# LVDS_Receiver_Data.net
KiCad netlist of a schematic drawn in Altium Designer
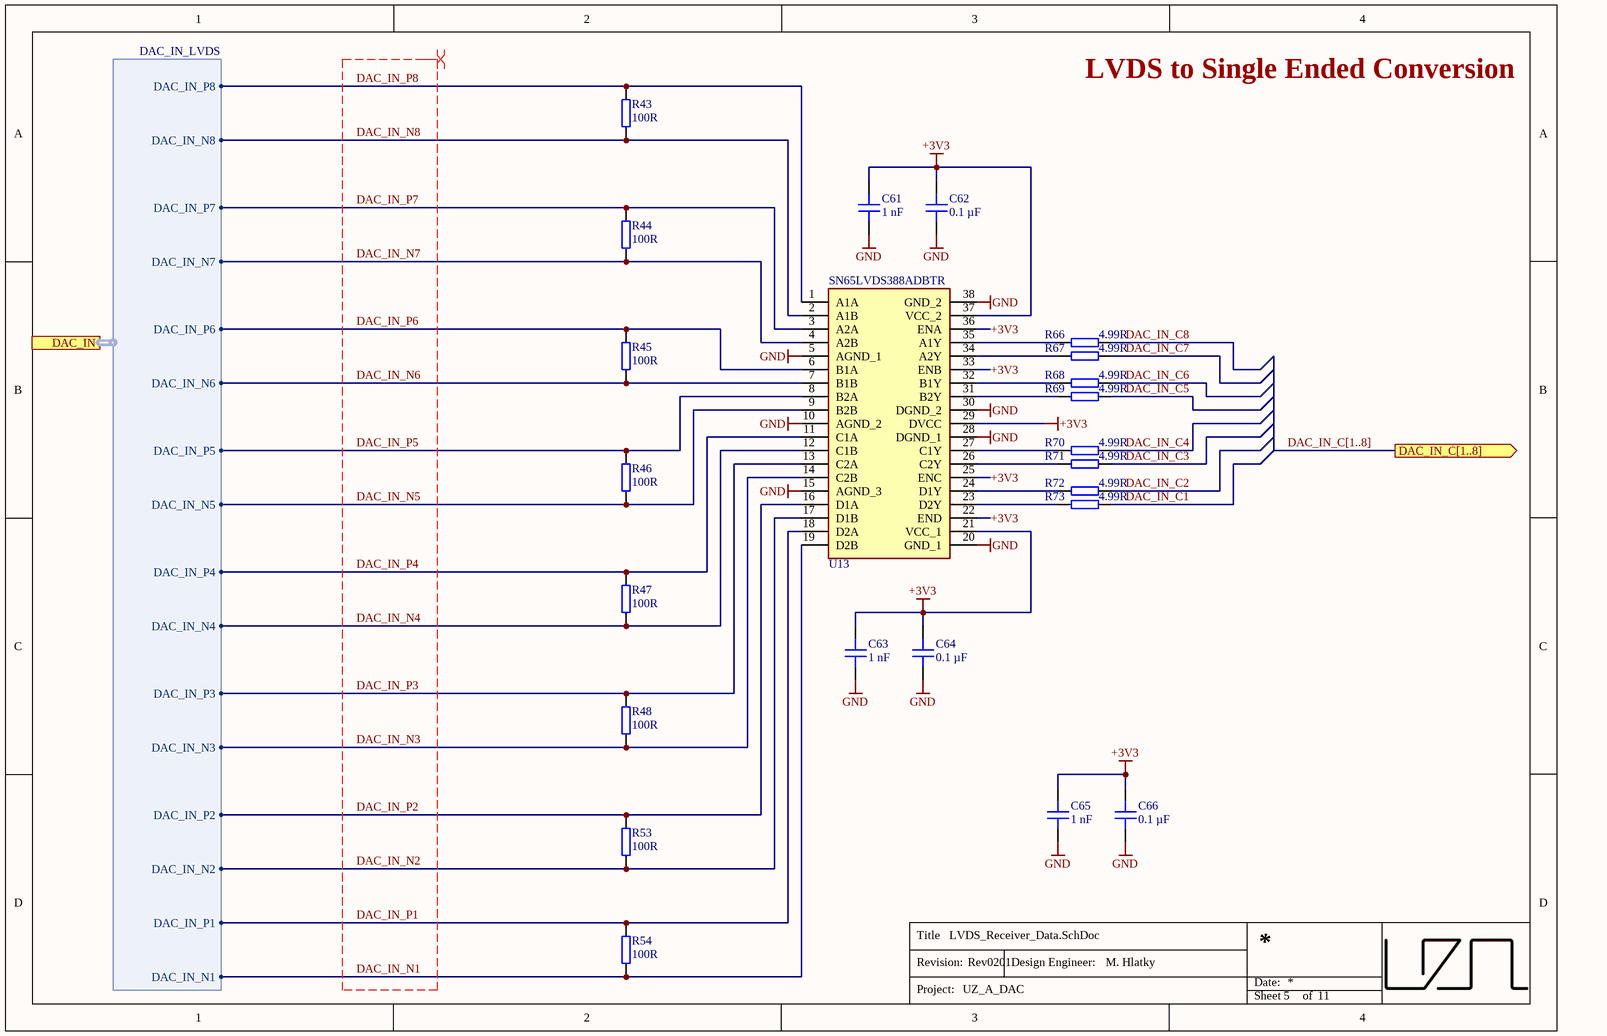
[diagram p0: LVDS_Receiver_Data.SchDoc]

(export (version "E")
  (design (tool "Eeschema 10.0.6"))
  (components
    (comp (ref "C61")
      (value "1 nF")
      (footprint "C_1206")
      (description "Capacitor 1206, 50 VDC, 1 nF, X7R")
      (fields
        (field (name "MANUFACTURER PART NUMBER") "12065C102KAT2A")
        (field (name "MANUFACTURER") "AVX")
        (field (name "CREATED FROM") "MGremer")
      )
      (libsource (lib "user") (part "Capacitor"))
    )
    (comp (ref "C62")
      (value "0.1 µF")
      (footprint "C_0603")
      (description "Capacitor 0603, 50 VDC, 0.1 µF, X7R")
      (fields
        (field (name "MANUFACTURER PART NUMBER") "C0603X104K5RAC7411")
        (field (name "MANUFACTURER") "KEMET")
        (field (name "CREATED FROM") "MGremer")
      )
      (libsource (lib "user") (part "Capacitor"))
    )
    (comp (ref "C63")
      (value "1 nF")
      (footprint "C_1206")
      (description "Capacitor 1206, 50 VDC, 1 nF, X7R")
      (fields
        (field (name "MANUFACTURER PART NUMBER") "12065C102KAT2A")
        (field (name "MANUFACTURER") "AVX")
        (field (name "CREATED FROM") "MGremer")
      )
      (libsource (lib "user") (part "Capacitor"))
    )
    (comp (ref "C64")
      (value "0.1 µF")
      (footprint "C_0603")
      (description "Capacitor 0603, 50 VDC, 0.1 µF, X7R")
      (fields
        (field (name "MANUFACTURER PART NUMBER") "C0603X104K5RAC7411")
        (field (name "MANUFACTURER") "KEMET")
        (field (name "CREATED FROM") "MGremer")
      )
      (libsource (lib "user") (part "Capacitor"))
    )
    (comp (ref "C65")
      (value "1 nF")
      (footprint "C_1206")
      (description "Capacitor 1206, 50 VDC, 1 nF, X7R")
      (fields
        (field (name "MANUFACTURER PART NUMBER") "12065C102KAT2A")
        (field (name "MANUFACTURER") "AVX")
        (field (name "CREATED FROM") "MGremer")
      )
      (libsource (lib "user") (part "Capacitor"))
    )
    (comp (ref "C66")
      (value "0.1 µF")
      (footprint "C_0603")
      (description "Capacitor 0603, 50 VDC, 0.1 µF, X7R")
      (fields
        (field (name "MANUFACTURER PART NUMBER") "C0603X104K5RAC7411")
        (field (name "MANUFACTURER") "KEMET")
        (field (name "CREATED FROM") "MGremer")
      )
      (libsource (lib "user") (part "Capacitor"))
    )
    (comp (ref "R43")
      (value "100R")
      (footprint "RES 0603_1608")
      (description "SMD resistor 1%")
      (fields
        (field (name "MANUFACTURER PART NUMBER") "AC0603FR-13100RL")
        (field (name "MANUFACTURER") "Yageo")
        (field (name "CREATED FROM") "MGremer")
      )
      (libsource (lib "user") (part "Resistor"))
    )
    (comp (ref "R44")
      (value "100R")
      (footprint "RES 0603_1608")
      (description "SMD resistor 1%")
      (fields
        (field (name "MANUFACTURER PART NUMBER") "AC0603FR-13100RL")
        (field (name "MANUFACTURER") "Yageo")
        (field (name "CREATED FROM") "MGremer")
      )
      (libsource (lib "user") (part "Resistor"))
    )
    (comp (ref "R45")
      (value "100R")
      (footprint "RES 0603_1608")
      (description "SMD resistor 1%")
      (fields
        (field (name "MANUFACTURER PART NUMBER") "AC0603FR-13100RL")
        (field (name "MANUFACTURER") "Yageo")
        (field (name "CREATED FROM") "MGremer")
      )
      (libsource (lib "user") (part "Resistor"))
    )
    (comp (ref "R46")
      (value "100R")
      (footprint "RES 0603_1608")
      (description "SMD resistor 1%")
      (fields
        (field (name "MANUFACTURER PART NUMBER") "AC0603FR-13100RL")
        (field (name "MANUFACTURER") "Yageo")
        (field (name "CREATED FROM") "MGremer")
      )
      (libsource (lib "user") (part "Resistor"))
    )
    (comp (ref "R47")
      (value "100R")
      (footprint "RES 0603_1608")
      (description "SMD resistor 1%")
      (fields
        (field (name "MANUFACTURER PART NUMBER") "AC0603FR-13100RL")
        (field (name "MANUFACTURER") "Yageo")
        (field (name "CREATED FROM") "MGremer")
      )
      (libsource (lib "user") (part "Resistor"))
    )
    (comp (ref "R48")
      (value "100R")
      (footprint "RES 0603_1608")
      (description "SMD resistor 1%")
      (fields
        (field (name "MANUFACTURER PART NUMBER") "AC0603FR-13100RL")
        (field (name "MANUFACTURER") "Yageo")
        (field (name "CREATED FROM") "MGremer")
      )
      (libsource (lib "user") (part "Resistor"))
    )
    (comp (ref "R53")
      (value "100R")
      (footprint "RES 0603_1608")
      (description "SMD resistor 1%")
      (fields
        (field (name "MANUFACTURER PART NUMBER") "AC0603FR-13100RL")
        (field (name "MANUFACTURER") "Yageo")
        (field (name "CREATED FROM") "MGremer")
      )
      (libsource (lib "user") (part "Resistor"))
    )
    (comp (ref "R54")
      (value "100R")
      (footprint "RES 0603_1608")
      (description "SMD resistor 1%")
      (fields
        (field (name "MANUFACTURER PART NUMBER") "AC0603FR-13100RL")
        (field (name "MANUFACTURER") "Yageo")
        (field (name "CREATED FROM") "MGremer")
      )
      (libsource (lib "user") (part "Resistor"))
    )
    (comp (ref "R66")
      (value "4.99R")
      (footprint "RES 0603_1608")
      (description "SMD resistor 1%")
      (fields
        (field (name "MANUFACTURER PART NUMBER") "CRCW06034R99FKEA")
        (field (name "MANUFACTURER") "Vishay / Dale")
        (field (name "CREATED FROM") "MGremer")
      )
      (libsource (lib "user") (part "Resistor"))
    )
    (comp (ref "R67")
      (value "4.99R")
      (footprint "RES 0603_1608")
      (description "SMD resistor 1%")
      (fields
        (field (name "MANUFACTURER PART NUMBER") "CRCW06034R99FKEA")
        (field (name "MANUFACTURER") "Vishay / Dale")
        (field (name "CREATED FROM") "MGremer")
      )
      (libsource (lib "user") (part "Resistor"))
    )
    (comp (ref "R68")
      (value "4.99R")
      (footprint "RES 0603_1608")
      (description "SMD resistor 1%")
      (fields
        (field (name "MANUFACTURER PART NUMBER") "CRCW06034R99FKEA")
        (field (name "MANUFACTURER") "Vishay / Dale")
        (field (name "CREATED FROM") "MGremer")
      )
      (libsource (lib "user") (part "Resistor"))
    )
    (comp (ref "R69")
      (value "4.99R")
      (footprint "RES 0603_1608")
      (description "SMD resistor 1%")
      (fields
        (field (name "MANUFACTURER PART NUMBER") "CRCW06034R99FKEA")
        (field (name "MANUFACTURER") "Vishay / Dale")
        (field (name "CREATED FROM") "MGremer")
      )
      (libsource (lib "user") (part "Resistor"))
    )
    (comp (ref "R70")
      (value "4.99R")
      (footprint "RES 0603_1608")
      (description "SMD resistor 1%")
      (fields
        (field (name "MANUFACTURER PART NUMBER") "CRCW06034R99FKEA")
        (field (name "MANUFACTURER") "Vishay / Dale")
        (field (name "CREATED FROM") "MGremer")
      )
      (libsource (lib "user") (part "Resistor"))
    )
    (comp (ref "R71")
      (value "4.99R")
      (footprint "RES 0603_1608")
      (description "SMD resistor 1%")
      (fields
        (field (name "MANUFACTURER PART NUMBER") "CRCW06034R99FKEA")
        (field (name "MANUFACTURER") "Vishay / Dale")
        (field (name "CREATED FROM") "MGremer")
      )
      (libsource (lib "user") (part "Resistor"))
    )
    (comp (ref "R72")
      (value "4.99R")
      (footprint "RES 0603_1608")
      (description "SMD resistor 1%")
      (fields
        (field (name "MANUFACTURER PART NUMBER") "CRCW06034R99FKEA")
        (field (name "MANUFACTURER") "Vishay / Dale")
        (field (name "CREATED FROM") "MGremer")
      )
      (libsource (lib "user") (part "Resistor"))
    )
    (comp (ref "R73")
      (value "4.99R")
      (footprint "RES 0603_1608")
      (description "SMD resistor 1%")
      (fields
        (field (name "MANUFACTURER PART NUMBER") "CRCW06034R99FKEA")
        (field (name "MANUFACTURER") "Vishay / Dale")
        (field (name "CREATED FROM") "MGremer")
      )
      (libsource (lib "user") (part "Resistor"))
    )
    (comp (ref "U13")
      (value "SN65LVDS388ADBTR")
      (footprint "SOP50P640X120-38N")
      (description "High-Speed Differential Line Receivers")
      (fields (field (name "MANUFACTURER") "TI") (field (name "CREATED FROM") "MHlatky"))
      (libsource (lib "user") (part "SN65LVDS388ADBTR"))
    )
  )
  (nets
    (net (code "2") (name "+3V3") (class "Default")
      (node (ref "C61") (pin "2") (pinfunction "2_2") (pintype "passive"))
      (node (ref "C62") (pin "1") (pinfunction "1_1") (pintype "passive"))
      (node (ref "C63") (pin "2") (pinfunction "2_2") (pintype "passive"))
      (node (ref "C64") (pin "1") (pinfunction "1_1") (pintype "passive"))
      (node (ref "C65") (pin "2") (pinfunction "2_2") (pintype "passive"))
      (node (ref "C66") (pin "1") (pinfunction "1_1") (pintype "passive"))
      (node (ref "U13") (pin "21") (pinfunction "VCC_1_21") (pintype "passive"))
      (node (ref "U13") (pin "22") (pinfunction "END_22") (pintype "passive"))
      (node (ref "U13") (pin "25") (pinfunction "ENC_25") (pintype "passive"))
      (node (ref "U13") (pin "29") (pinfunction "DVCC_29") (pintype "passive"))
      (node (ref "U13") (pin "33") (pinfunction "ENB_33") (pintype "passive"))
      (node (ref "U13") (pin "36") (pinfunction "ENA_36") (pintype "passive"))
      (node (ref "U13") (pin "37") (pinfunction "VCC_2_37") (pintype "passive"))
    )
    (net (code "3") (name "/DAC_IN_C1") (class "Default")
      (node (ref "R73") (pin "2") (pinfunction "2_2") (pintype "passive"))
    )
    (net (code "4") (name "/DAC_IN_C2") (class "Default")
      (node (ref "R72") (pin "2") (pinfunction "2_2") (pintype "passive"))
    )
    (net (code "5") (name "/DAC_IN_C3") (class "Default")
      (node (ref "R71") (pin "2") (pinfunction "2_2") (pintype "passive"))
    )
    (net (code "6") (name "/DAC_IN_C4") (class "Default")
      (node (ref "R70") (pin "2") (pinfunction "2_2") (pintype "passive"))
    )
    (net (code "7") (name "/DAC_IN_C5") (class "Default")
      (node (ref "R69") (pin "2") (pinfunction "2_2") (pintype "passive"))
    )
    (net (code "8") (name "/DAC_IN_C6") (class "Default")
      (node (ref "R68") (pin "2") (pinfunction "2_2") (pintype "passive"))
    )
    (net (code "9") (name "/DAC_IN_C7") (class "Default")
      (node (ref "R67") (pin "2") (pinfunction "2_2") (pintype "passive"))
    )
    (net (code "10") (name "/DAC_IN_C8") (class "Default")
      (node (ref "R66") (pin "2") (pinfunction "2_2") (pintype "passive"))
    )
    (net (code "12") (name "/DAC_IN_N1") (class "Default")
      (node (ref "R54") (pin "1") (pinfunction "1_1") (pintype "passive"))
      (node (ref "U13") (pin "19") (pinfunction "D2B_19") (pintype "passive"))
    )
    (net (code "13") (name "/DAC_IN_N2") (class "Default")
      (node (ref "R53") (pin "1") (pinfunction "1_1") (pintype "passive"))
      (node (ref "U13") (pin "17") (pinfunction "D1B_17") (pintype "passive"))
    )
    (net (code "14") (name "/DAC_IN_N3") (class "Default")
      (node (ref "R48") (pin "1") (pinfunction "1_1") (pintype "passive"))
      (node (ref "U13") (pin "14") (pinfunction "C2B_14") (pintype "passive"))
    )
    (net (code "15") (name "/DAC_IN_N4") (class "Default")
      (node (ref "R47") (pin "1") (pinfunction "1_1") (pintype "passive"))
      (node (ref "U13") (pin "12") (pinfunction "C1B_12") (pintype "passive"))
    )
    (net (code "16") (name "/DAC_IN_N5") (class "Default")
      (node (ref "R46") (pin "1") (pinfunction "1_1") (pintype "passive"))
      (node (ref "U13") (pin "9") (pinfunction "B2B_9") (pintype "passive"))
    )
    (net (code "17") (name "/DAC_IN_N6") (class "Default")
      (node (ref "R45") (pin "1") (pinfunction "1_1") (pintype "passive"))
      (node (ref "U13") (pin "7") (pinfunction "B1B_7") (pintype "passive"))
    )
    (net (code "18") (name "/DAC_IN_N7") (class "Default")
      (node (ref "R44") (pin "1") (pinfunction "1_1") (pintype "passive"))
      (node (ref "U13") (pin "4") (pinfunction "A2B_4") (pintype "passive"))
    )
    (net (code "19") (name "/DAC_IN_N8") (class "Default")
      (node (ref "R43") (pin "1") (pinfunction "1_1") (pintype "passive"))
      (node (ref "U13") (pin "2") (pinfunction "A1B_2") (pintype "passive"))
    )
    (net (code "20") (name "/DAC_IN_P1") (class "Default")
      (node (ref "R54") (pin "2") (pinfunction "2_2") (pintype "passive"))
      (node (ref "U13") (pin "18") (pinfunction "D2A_18") (pintype "passive"))
    )
    (net (code "21") (name "/DAC_IN_P2") (class "Default")
      (node (ref "R53") (pin "2") (pinfunction "2_2") (pintype "passive"))
      (node (ref "U13") (pin "16") (pinfunction "D1A_16") (pintype "passive"))
    )
    (net (code "22") (name "/DAC_IN_P3") (class "Default")
      (node (ref "R48") (pin "2") (pinfunction "2_2") (pintype "passive"))
      (node (ref "U13") (pin "13") (pinfunction "C2A_13") (pintype "passive"))
    )
    (net (code "23") (name "/DAC_IN_P4") (class "Default")
      (node (ref "R47") (pin "2") (pinfunction "2_2") (pintype "passive"))
      (node (ref "U13") (pin "11") (pinfunction "C1A_11") (pintype "passive"))
    )
    (net (code "24") (name "/DAC_IN_P5") (class "Default")
      (node (ref "R46") (pin "2") (pinfunction "2_2") (pintype "passive"))
      (node (ref "U13") (pin "8") (pinfunction "B2A_8") (pintype "passive"))
    )
    (net (code "25") (name "/DAC_IN_P6") (class "Default")
      (node (ref "R45") (pin "2") (pinfunction "2_2") (pintype "passive"))
      (node (ref "U13") (pin "6") (pinfunction "B1A_6") (pintype "passive"))
    )
    (net (code "26") (name "/DAC_IN_P7") (class "Default")
      (node (ref "R44") (pin "2") (pinfunction "2_2") (pintype "passive"))
      (node (ref "U13") (pin "3") (pinfunction "A2A_3") (pintype "passive"))
    )
    (net (code "27") (name "/DAC_IN_P8") (class "Default")
      (node (ref "R43") (pin "2") (pinfunction "2_2") (pintype "passive"))
      (node (ref "U13") (pin "1") (pinfunction "A1A_1") (pintype "passive"))
    )
    (net (code "29") (name "GND") (class "Default")
      (node (ref "C61") (pin "1") (pinfunction "1_1") (pintype "passive"))
      (node (ref "C62") (pin "2") (pinfunction "2_2") (pintype "passive"))
      (node (ref "C63") (pin "1") (pinfunction "1_1") (pintype "passive"))
      (node (ref "C64") (pin "2") (pinfunction "2_2") (pintype "passive"))
      (node (ref "C65") (pin "1") (pinfunction "1_1") (pintype "passive"))
      (node (ref "C66") (pin "2") (pinfunction "2_2") (pintype "passive"))
      (node (ref "U13") (pin "10") (pinfunction "AGND_2_10") (pintype "passive"))
      (node (ref "U13") (pin "15") (pinfunction "AGND_3_15") (pintype "passive"))
      (node (ref "U13") (pin "20") (pinfunction "GND_1_20") (pintype "passive"))
      (node (ref "U13") (pin "28") (pinfunction "DGND_1_28") (pintype "passive"))
      (node (ref "U13") (pin "30") (pinfunction "DGND_2_30") (pintype "passive"))
      (node (ref "U13") (pin "38") (pinfunction "GND_2_38") (pintype "passive"))
      (node (ref "U13") (pin "5") (pinfunction "AGND_1_5") (pintype "passive"))
    )
    (net (code "30") (name "Net-(U13-A1Y)") (class "Default")
      (node (ref "R66") (pin "1") (pinfunction "1_1") (pintype "passive"))
      (node (ref "U13") (pin "35") (pinfunction "A1Y_35") (pintype "passive"))
    )
    (net (code "31") (name "Net-(U13-A2Y)") (class "Default")
      (node (ref "R67") (pin "1") (pinfunction "1_1") (pintype "passive"))
      (node (ref "U13") (pin "34") (pinfunction "A2Y_34") (pintype "passive"))
    )
    (net (code "32") (name "Net-(U13-B1Y)") (class "Default")
      (node (ref "R68") (pin "1") (pinfunction "1_1") (pintype "passive"))
      (node (ref "U13") (pin "32") (pinfunction "B1Y_32") (pintype "passive"))
    )
    (net (code "33") (name "Net-(U13-B2Y)") (class "Default")
      (node (ref "R69") (pin "1") (pinfunction "1_1") (pintype "passive"))
      (node (ref "U13") (pin "31") (pinfunction "B2Y_31") (pintype "passive"))
    )
    (net (code "34") (name "Net-(U13-C1Y)") (class "Default")
      (node (ref "R70") (pin "1") (pinfunction "1_1") (pintype "passive"))
      (node (ref "U13") (pin "27") (pinfunction "C1Y_27") (pintype "passive"))
    )
    (net (code "35") (name "Net-(U13-C2Y)") (class "Default")
      (node (ref "R71") (pin "1") (pinfunction "1_1") (pintype "passive"))
      (node (ref "U13") (pin "26") (pinfunction "C2Y_26") (pintype "passive"))
    )
    (net (code "36") (name "Net-(U13-D1Y)") (class "Default")
      (node (ref "R72") (pin "1") (pinfunction "1_1") (pintype "passive"))
      (node (ref "U13") (pin "24") (pinfunction "D1Y_24") (pintype "passive"))
    )
    (net (code "37") (name "Net-(U13-D2Y)") (class "Default")
      (node (ref "R73") (pin "1") (pinfunction "1_1") (pintype "passive"))
      (node (ref "U13") (pin "23") (pinfunction "D2Y_23") (pintype "passive"))
    )
  )
)
